# FAN_Conrol.net
KiCad netlist of a schematic drawn in Altium Designer
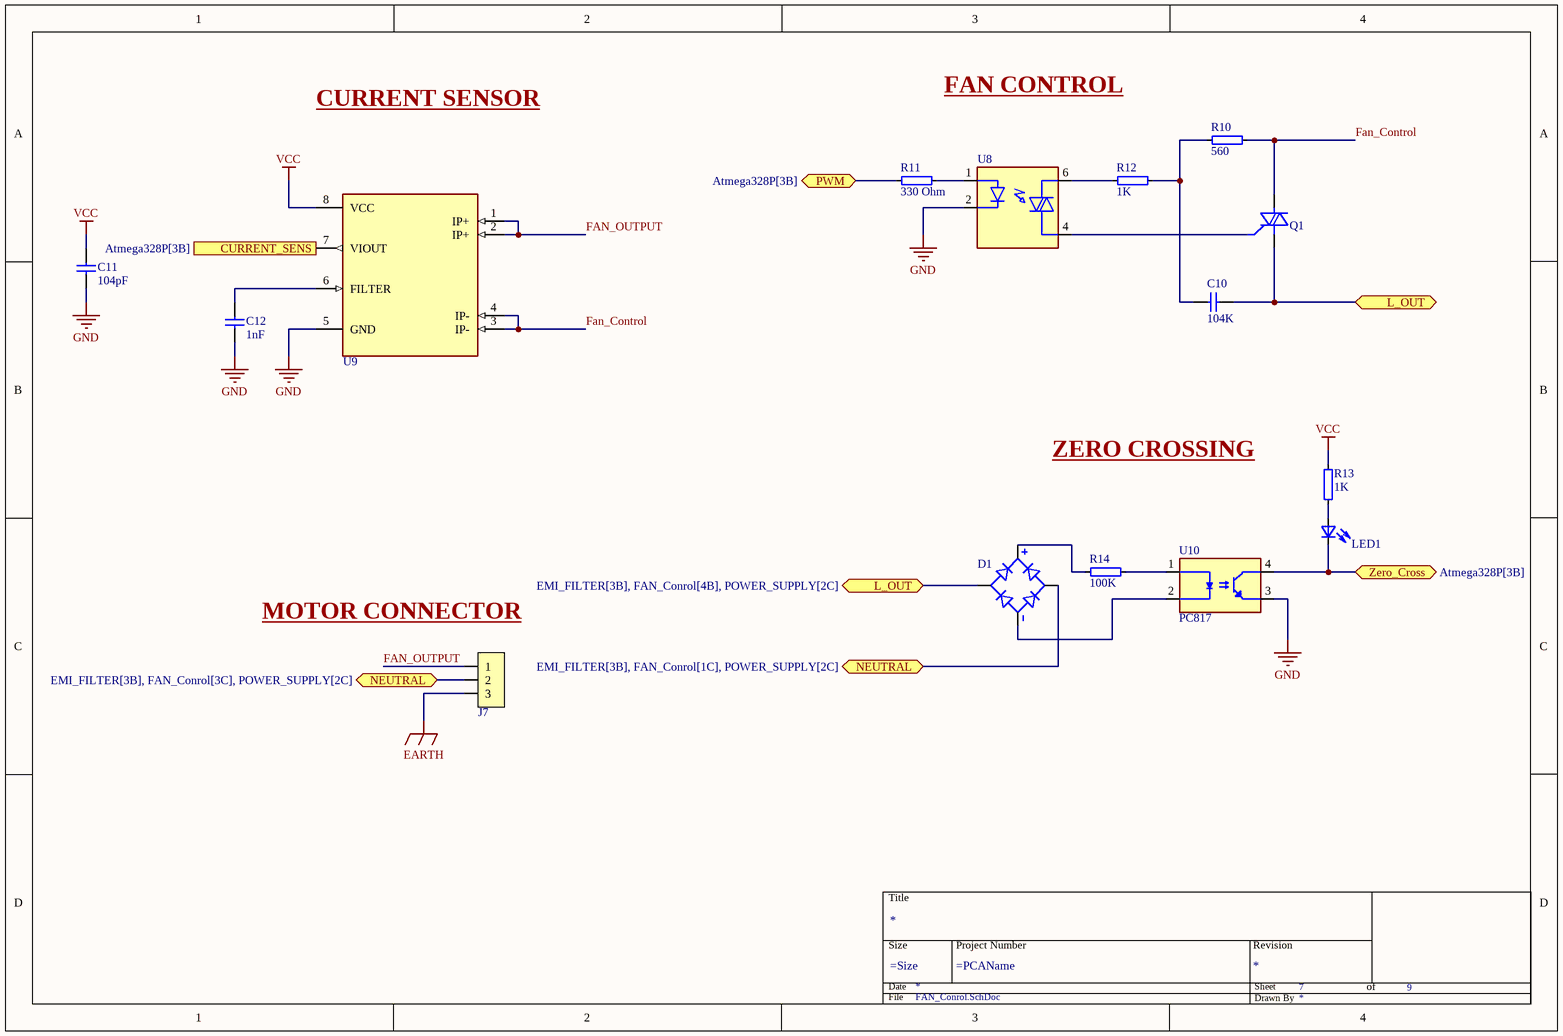
[diagram p0: FAN_Conrol.SchDoc]

(export (version "E")
  (design (tool "Eeschema 10.0.6"))
  (components
    (comp (ref "*") (value "Title Block") (libsource (lib "HEPA_LIB") (part "Title Block")))
    (comp (ref "C10")
      (value "104K")
      (footprint "CAPRR1500W60L1850T800H1650")
      (description "Capacitor, Metalized Polypropylene Film,300VAC, 0.1uF, +-10%")
      (fields (field (name "PART NUMBER") "100nF 300V") (field (name "PUBLISHER") "Metal Circuits"))
      (libsource (lib "HEPA_LIB") (part "0.1uF 300V"))
    )
    (comp (ref "C11")
      (value "104pF")
      (footprint "CAPC2012X140N")
      (fields (field (name "PART NUMBER") "CAP_0805") (field (name "PUBLISHER") "Metal Circuits"))
      (libsource (lib "HEPA_LIB") (part "CAP_0805"))
    )
    (comp (ref "C12")
      (value "1nF")
      (footprint "CAPC2012X140N")
      (fields (field (name "PART NUMBER") "CAP_0805") (field (name "PUBLISHER") "Metal Circuits"))
      (libsource (lib "HEPA_LIB") (part "CAP_0805"))
    )
    (comp (ref "D1")
      (value "DB107-BP")
      (footprint "DIP825W50P509L880H320Q4")
      (description "Bridge Rectifier Single Phase Standard 1 kV Through Hole DB-1")
      (fields (field (name "MANUFACTURER") "MCC") (field (name "PUBLISHER") "Metal Circuits"))
      (libsource (lib "HEPA_LIB") (part "DB107-BP"))
    )
    (comp (ref "J7")
      (value "1935174")
      (footprint "PHOENIX_1935174")
      (description "3 Position Wire to Board Terminal Block Horizontal with Board 0.197\" (5.00mm) Through Hole")
      (fields (field (name "MANUFACTURER") "Phoenix Contact") (field (name "PUBLISHER") "Metal Circuits"))
      (libsource (lib "HEPA_LIB") (part "1935174"))
    )
    (comp (ref "LED1")
      (value "LED_0603")
      (footprint "LED_KP-2012")
      (description "LED SMD 0603")
      (fields (field (name "PUBLISHER") "Metal Circuits"))
      (libsource (lib "HEPA_LIB") (part "LED_0603"))
    )
    (comp (ref "Q1")
      (value "BTA16-600CW3G")
      (footprint "TO254P1028X482X1968-3")
      (description "TRIAC Standard 600V 16A Through Hole TO-220AB")
      (fields (field (name "MANUFACTURER") "Littelfuse Inc.") (field (name "PUBLISHER") "Metal Circuits"))
      (libsource (lib "HEPA_LIB") (part "BTA16-600CW3G"))
    )
    (comp (ref "R10")
      (value "560")
      (footprint "RES_ROX2S_TYCO_TYC")
      (description "Carbon Film Through Hole Resistor 2Watt 1%")
      (fields (field (name "PART NUMBER") "RES 2 Watt") (field (name "PUBLISHER") "Metal Circuits"))
      (libsource (lib "HEPA_LIB") (part "RES 2Watt"))
    )
    (comp (ref "R11")
      (value "330 Ohm")
      (footprint "RESC2012X65N")
      (description "RES SMD 1% 1/10W 0805")
      (fields (field (name "PART NUMBER") "RES_0805") (field (name "PUBLISHER") "Metal Circuits"))
      (libsource (lib "HEPA_LIB") (part "RES_0805"))
    )
    (comp (ref "R12")
      (value "1K")
      (footprint "RES_ROX2S_TYCO_TYC")
      (description "Carbon Film Through Hole Resistor 1Watt 1%")
      (fields (field (name "PART NUMBER") "RES 1 Watt") (field (name "PUBLISHER") "Metal Circuits"))
      (libsource (lib "HEPA_LIB") (part "RES 1Watt"))
    )
    (comp (ref "R13")
      (value "1K")
      (footprint "RESC2012X65N")
      (description "RES SMD 1% 1/10W 0805")
      (fields (field (name "PART NUMBER") "RES_0805") (field (name "PUBLISHER") "Metal Circuits"))
      (libsource (lib "HEPA_LIB") (part "RES_0805"))
    )
    (comp (ref "R14")
      (value "100K")
      (footprint "RES_ROX2S_TYCO_TYC")
      (description "Carbon Film Through Hole Resistor 1Watt 1%")
      (fields (field (name "PART NUMBER") "RES 1 Watt") (field (name "PUBLISHER") "Metal Circuits"))
      (libsource (lib "HEPA_LIB") (part "RES 1Watt"))
    )
    (comp (ref "U8")
      (value "MOC3021")
      (footprint "DIP762W45P254L889H508Q6")
      (description "Optoisolator Triac Output 5000Vrms 1 Channel 6-DIP")
      (fields (field (name "MANUFACTURER") "Lite-On") (field (name "PUBLISHER") "Metal Circuits"))
      (libsource (lib "HEPA_LIB") (part "MOC3021"))
    )
    (comp (ref "U9")
      (value "ACS712ELCTR")
      (footprint "SOIC127P600X175-8N")
      (description "Current Sensor 5A 1 Channel Hall Effect, Open Loop Bidirectional 8-SOIC (0.154\", 3.90mm Width)")
      (fields (field (name "PUBLISHER") "Metal Circuits"))
      (libsource (lib "HEPA_LIB") (part "ACS712ELCTR-05B-T"))
    )
    (comp (ref "U10")
      (value "PC817")
      (footprint "DIP762W50P254L495H455Q4")
      (description "Optoisolator Transistor Output - 1 Channel 4-DIP")
      (fields (field (name "MANUFACTURER") "SHARP") (field (name "PUBLISHER") "Metal Circuits"))
      (libsource (lib "HEPA_LIB") (part "PC817"))
    )
  )
  (nets
    (net (code "1") (name "/CURRENT_SENS") (class "Default")
      (node (ref "U9") (pin "7") (pinfunction "VIOUT_7") (pintype "output"))
    )
    (net (code "2") (name "/FAN_OUTPUT") (class "Default")
      (node (ref "J7") (pin "1") (pinfunction "1_1") (pintype "passive"))
      (node (ref "U9") (pin "1") (pinfunction "IP+_1") (pintype "input"))
      (node (ref "U9") (pin "2") (pinfunction "IP+_2") (pintype "input"))
    )
    (net (code "3") (name "/Fan_Control") (class "Default")
      (node (ref "Q1") (pin "2") (pinfunction "MT2_2") (pintype "passive"))
      (node (ref "R10") (pin "2") (pinfunction "2_2") (pintype "passive"))
      (node (ref "U9") (pin "3") (pinfunction "IP-_3") (pintype "input"))
      (node (ref "U9") (pin "4") (pinfunction "IP-_4") (pintype "input"))
    )
    (net (code "4") (name "/L_OUT") (class "Default")
      (node (ref "C10") (pin "2") (pinfunction "2_2") (pintype "passive"))
      (node (ref "D1") (pin "4") (pinfunction "AC2_4") (pintype "passive"))
      (node (ref "Q1") (pin "1") (pinfunction "MT1_1") (pintype "passive"))
    )
    (net (code "5") (name "/NEUTRAL") (class "Default")
      (node (ref "D1") (pin "3") (pinfunction "AC1_3") (pintype "passive"))
      (node (ref "J7") (pin "2") (pinfunction "2_2") (pintype "passive"))
    )
    (net (code "6") (name "/PWM") (class "Default")
      (node (ref "R11") (pin "1") (pinfunction "1_1") (pintype "passive"))
    )
    (net (code "7") (name "/Zero_Cross") (class "Default")
      (node (ref "LED1") (pin "2") (pinfunction "Cathode_2") (pintype "passive"))
      (node (ref "U10") (pin "4") (pinfunction "COLLECTOR_4") (pintype "passive"))
    )
    (net (code "8") (name "EARTH") (class "Default")
      (node (ref "J7") (pin "3") (pinfunction "3_3") (pintype "passive"))
    )
    (net (code "9") (name "GND") (class "Default")
      (node (ref "C11") (pin "1") (pinfunction "1_1") (pintype "passive"))
      (node (ref "C12") (pin "1") (pinfunction "1_1") (pintype "passive"))
      (node (ref "U10") (pin "3") (pinfunction "EMITTER_3") (pintype "passive"))
      (node (ref "U8") (pin "2") (pinfunction "CATODE_2") (pintype "passive"))
      (node (ref "U9") (pin "5") (pinfunction "GND_5") (pintype "power_in"))
    )
    (net (code "10") (name "Net-(C10-Pad1)") (class "Default")
      (node (ref "C10") (pin "1") (pinfunction "1_1") (pintype "passive"))
      (node (ref "R10") (pin "1") (pinfunction "1_1") (pintype "passive"))
      (node (ref "R12") (pin "2") (pinfunction "2_2") (pintype "passive"))
    )
    (net (code "11") (name "Net-(D1-NEG)") (class "Default")
      (node (ref "D1") (pin "2") (pinfunction "NEG_2") (pintype "passive"))
      (node (ref "U10") (pin "2") (pinfunction "CATHODE_2") (pintype "passive"))
    )
    (net (code "12") (name "Net-(D1-POS)") (class "Default")
      (node (ref "D1") (pin "1") (pinfunction "POS_1") (pintype "passive"))
      (node (ref "R14") (pin "1") (pinfunction "1_1") (pintype "passive"))
    )
    (net (code "13") (name "Net-(LED1-Anode)") (class "Default")
      (node (ref "LED1") (pin "1") (pinfunction "Anode_1") (pintype "passive"))
      (node (ref "R13") (pin "1") (pinfunction "1_1") (pintype "passive"))
    )
    (net (code "14") (name "Net-(Q1-G)") (class "Default")
      (node (ref "Q1") (pin "3") (pinfunction "G_3") (pintype "passive"))
      (node (ref "U8") (pin "4") (pinfunction "MAIN_TERM2_4") (pintype "passive"))
    )
    (net (code "15") (name "Net-(U8-ANODE)") (class "Default")
      (node (ref "R11") (pin "2") (pinfunction "2_2") (pintype "passive"))
      (node (ref "U8") (pin "1") (pinfunction "ANODE_1") (pintype "passive"))
    )
    (net (code "16") (name "Net-(U8-MAIN_TERM1)") (class "Default")
      (node (ref "R12") (pin "1") (pinfunction "1_1") (pintype "passive"))
      (node (ref "U8") (pin "6") (pinfunction "MAIN_TERM1_6") (pintype "passive"))
    )
    (net (code "17") (name "Net-(U9-FILTER)") (class "Default")
      (node (ref "C12") (pin "2") (pinfunction "2_2") (pintype "passive"))
      (node (ref "U9") (pin "6") (pinfunction "FILTER_6") (pintype "input"))
    )
    (net (code "18") (name "Net-(U10-ANODE)") (class "Default")
      (node (ref "R14") (pin "2") (pinfunction "2_2") (pintype "passive"))
      (node (ref "U10") (pin "1") (pinfunction "ANODE_1") (pintype "passive"))
    )
    (net (code "19") (name "VCC") (class "Default")
      (node (ref "C11") (pin "2") (pinfunction "2_2") (pintype "passive"))
      (node (ref "R13") (pin "2") (pinfunction "2_2") (pintype "passive"))
      (node (ref "U9") (pin "8") (pinfunction "VCC_8") (pintype "power_in"))
    )
  )
)
